# Untitled_b2.net
KiCad netlist of a schematic drawn in EAGLE
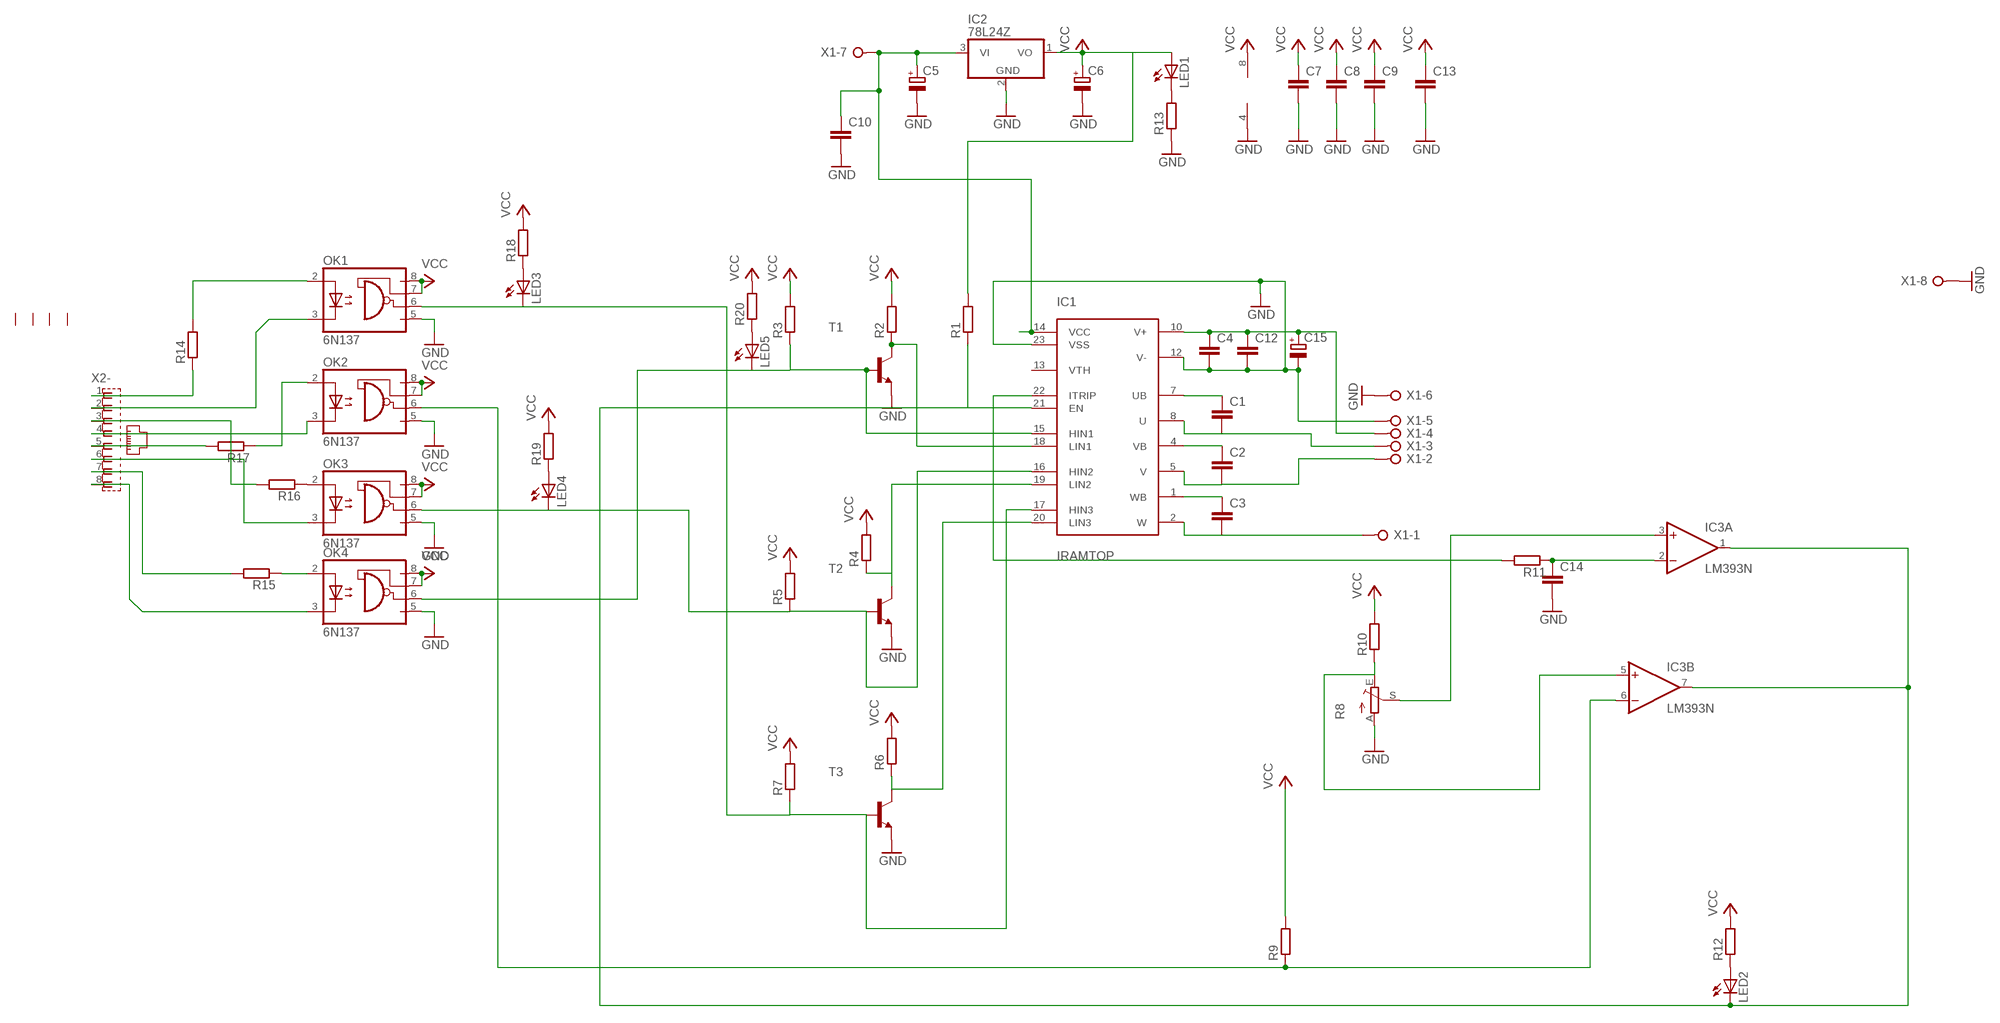
[diagram p0: schematic, sheet 1]

(export (version "E")
  (design (tool "Eeschema 10.0.6"))
  (components
    (comp (ref "C1")
      (value "C5/5")
      (footprint "eagle-import:C5B5")
      (libsource (lib "eagle-import") (part "C5/5"))
    )
    (comp (ref "C2")
      (value "C5/5")
      (footprint "eagle-import:C5B5")
      (libsource (lib "eagle-import") (part "C5/5"))
    )
    (comp (ref "C3")
      (value "C5/5")
      (footprint "eagle-import:C5B5")
      (libsource (lib "eagle-import") (part "C5/5"))
    )
    (comp (ref "C4")
      (value "C5/5")
      (footprint "eagle-import:C5B5")
      (libsource (lib "eagle-import") (part "C5/5"))
    )
    (comp (ref "C5")
      (value "CPOL-EUE2.5-5")
      (footprint "eagle-import:E2,5-5")
      (libsource (lib "eagle-import") (part "CPOL-EUE2.5-5"))
    )
    (comp (ref "C6")
      (value "CPOL-EUE2.5-5")
      (footprint "eagle-import:E2,5-5")
      (libsource (lib "eagle-import") (part "CPOL-EUE2.5-5"))
    )
    (comp (ref "C7")
      (value "C-EU050-025X075")
      (footprint "eagle-import:C050-025X075")
      (libsource (lib "eagle-import") (part "C-EU050-025X075"))
    )
    (comp (ref "C8")
      (value "C-EU050-025X075")
      (footprint "eagle-import:C050-025X075")
      (libsource (lib "eagle-import") (part "C-EU050-025X075"))
    )
    (comp (ref "C9")
      (value "C-EU050-025X075")
      (footprint "eagle-import:C050-025X075")
      (libsource (lib "eagle-import") (part "C-EU050-025X075"))
    )
    (comp (ref "C10")
      (value "C-EU050-025X075")
      (footprint "eagle-import:C050-025X075")
      (libsource (lib "eagle-import") (part "C-EU050-025X075"))
    )
    (comp (ref "C12")
      (value "C-EU150-054X183")
      (footprint "eagle-import:C150-054X183")
      (libsource (lib "eagle-import") (part "C-EU150-054X183"))
    )
    (comp (ref "C13")
      (value "C-EU050-025X075")
      (footprint "eagle-import:C050-025X075")
      (libsource (lib "eagle-import") (part "C-EU050-025X075"))
    )
    (comp (ref "C14")
      (value "C-EU050-025X075")
      (footprint "eagle-import:C050-025X075")
      (libsource (lib "eagle-import") (part "C-EU050-025X075"))
    )
    (comp (ref "C15")
      (value "CPOL-EUE10-25")
      (footprint "eagle-import:EB25D")
      (libsource (lib "eagle-import") (part "CPOL-EUE10-25"))
    )
    (comp (ref "IC1")
      (value "IRAMTOP")
      (footprint "eagle-import:SIP23_TOP")
      (libsource (lib "eagle-import") (part "IRAMTOP"))
    )
    (comp (ref "IC2")
      (value "78L24Z")
      (footprint "eagle-import:TO92")
      (libsource (lib "eagle-import") (part "78ZL24"))
    )
    (comp (ref "IC3")
      (value "LM393N")
      (footprint "eagle-import:DIL08")
      (libsource (lib "eagle-import") (part "LM393N"))
    )
    (comp (ref "LED1")
      (value "LED5MM")
      (footprint "eagle-import:LED5MM")
      (libsource (lib "eagle-import") (part "LED5MM"))
    )
    (comp (ref "LED2")
      (value "LED5MM")
      (footprint "eagle-import:LED5MM")
      (libsource (lib "eagle-import") (part "LED5MM"))
    )
    (comp (ref "LED3")
      (value "LED5MM")
      (footprint "eagle-import:LED5MM")
      (libsource (lib "eagle-import") (part "LED5MM"))
    )
    (comp (ref "LED4")
      (value "LED5MM")
      (footprint "eagle-import:LED5MM")
      (libsource (lib "eagle-import") (part "LED5MM"))
    )
    (comp (ref "LED5")
      (value "LED5MM")
      (footprint "eagle-import:LED5MM")
      (libsource (lib "eagle-import") (part "LED5MM"))
    )
    (comp (ref "OK1")
      (value "6N137")
      (footprint "eagle-import:DIL08")
      (libsource (lib "eagle-import") (part "6N137"))
    )
    (comp (ref "OK2")
      (value "6N137")
      (footprint "eagle-import:DIL08")
      (libsource (lib "eagle-import") (part "6N137"))
    )
    (comp (ref "OK3")
      (value "6N137")
      (footprint "eagle-import:DIL08")
      (libsource (lib "eagle-import") (part "6N137"))
    )
    (comp (ref "OK4")
      (value "6N137")
      (footprint "eagle-import:DIL08")
      (libsource (lib "eagle-import") (part "6N137"))
    )
    (comp (ref "R1")
      (value "R-EU_0204/7")
      (footprint "eagle-import:0204_7")
      (libsource (lib "eagle-import") (part "R-EU_0204/7"))
    )
    (comp (ref "R2")
      (value "R-EU_0204/7")
      (footprint "eagle-import:0204_7")
      (libsource (lib "eagle-import") (part "R-EU_0204/7"))
    )
    (comp (ref "R3")
      (value "R-EU_0204/7")
      (footprint "eagle-import:0204_7")
      (libsource (lib "eagle-import") (part "R-EU_0204/7"))
    )
    (comp (ref "R4")
      (value "R-EU_0204/7")
      (footprint "eagle-import:0204_7")
      (libsource (lib "eagle-import") (part "R-EU_0204/7"))
    )
    (comp (ref "R5")
      (value "R-EU_0204/7")
      (footprint "eagle-import:0204_7")
      (libsource (lib "eagle-import") (part "R-EU_0204/7"))
    )
    (comp (ref "R6")
      (value "R-EU_0204/7")
      (footprint "eagle-import:0204_7")
      (libsource (lib "eagle-import") (part "R-EU_0204/7"))
    )
    (comp (ref "R7")
      (value "R-EU_0204/7")
      (footprint "eagle-import:0204_7")
      (libsource (lib "eagle-import") (part "R-EU_0204/7"))
    )
    (comp (ref "R8")
      (value "TRIM_EU-CA6V")
      (footprint "eagle-import:CA6V")
      (libsource (lib "eagle-import") (part "TRIM_EU-CA6V"))
    )
    (comp (ref "R9")
      (value "R-EU_0204/7")
      (footprint "eagle-import:0204_7")
      (libsource (lib "eagle-import") (part "R-EU_0204/7"))
    )
    (comp (ref "R10")
      (value "R-EU_0204/7")
      (footprint "eagle-import:0204_7")
      (libsource (lib "eagle-import") (part "R-EU_0204/7"))
    )
    (comp (ref "R11")
      (value "R-EU_0204/7")
      (footprint "eagle-import:0204_7")
      (libsource (lib "eagle-import") (part "R-EU_0204/7"))
    )
    (comp (ref "R12")
      (value "R-EU_0204/7")
      (footprint "eagle-import:0204_7")
      (libsource (lib "eagle-import") (part "R-EU_0204/7"))
    )
    (comp (ref "R13")
      (value "R-EU_0204/7")
      (footprint "eagle-import:0204_7")
      (libsource (lib "eagle-import") (part "R-EU_0204/7"))
    )
    (comp (ref "R14")
      (value "R-EU_0204/2V")
      (footprint "eagle-import:0204V")
      (libsource (lib "eagle-import") (part "R-EU_0204/2V"))
    )
    (comp (ref "R15")
      (value "R-EU_0204/2V")
      (footprint "eagle-import:0204V")
      (libsource (lib "eagle-import") (part "R-EU_0204/2V"))
    )
    (comp (ref "R16")
      (value "R-EU_0204/2V")
      (footprint "eagle-import:0204V")
      (libsource (lib "eagle-import") (part "R-EU_0204/2V"))
    )
    (comp (ref "R17")
      (value "R-EU_0204/2V")
      (footprint "eagle-import:0204V")
      (libsource (lib "eagle-import") (part "R-EU_0204/2V"))
    )
    (comp (ref "R18")
      (value "R-EU_0204/7")
      (footprint "eagle-import:0204_7")
      (libsource (lib "eagle-import") (part "R-EU_0204/7"))
    )
    (comp (ref "R19")
      (value "R-EU_0204/7")
      (footprint "eagle-import:0204_7")
      (libsource (lib "eagle-import") (part "R-EU_0204/7"))
    )
    (comp (ref "R20")
      (value "R-EU_0204/7")
      (footprint "eagle-import:0204_7")
      (libsource (lib "eagle-import") (part "R-EU_0204/7"))
    )
    (comp (ref "T1")
      (value "BC547-NPN-TO92-CBE")
      (footprint "eagle-import:TO92-CBE")
      (libsource (lib "eagle-import") (part "-NPN-TO92-CBEBC547"))
    )
    (comp (ref "T2")
      (value "BC547-NPN-TO92-CBE")
      (footprint "eagle-import:TO92-CBE")
      (libsource (lib "eagle-import") (part "-NPN-TO92-CBEBC547"))
    )
    (comp (ref "T3")
      (value "BC547-NPN-TO92-CBE")
      (footprint "eagle-import:TO92-CBE")
      (libsource (lib "eagle-import") (part "-NPN-TO92-CBEBC547"))
    )
    (comp (ref "X1")
      (value "W237-08P")
      (footprint "eagle-import:W237-8P")
      (libsource (lib "eagle-import") (part "W237-08P"))
    )
    (comp (ref "X2")
      (value "RJ45")
      (footprint "eagle-import:RJ45")
      (libsource (lib "eagle-import") (part "RJ45"))
    )
  )
  (nets
    (net (code "1") (name "GND") (class "Default")
      (node (ref "C10") (pin "2") (pinfunction "2_2") (pintype "passive"))
      (node (ref "C12") (pin "2") (pinfunction "2_2") (pintype "passive"))
      (node (ref "C13") (pin "2") (pinfunction "2_2") (pintype "passive"))
      (node (ref "C14") (pin "2") (pinfunction "2_2") (pintype "passive"))
      (node (ref "C15") (pin "-") (pinfunction "-_-") (pintype "passive"))
      (node (ref "C4") (pin "2") (pinfunction "2_2") (pintype "passive"))
      (node (ref "C5") (pin "-") (pinfunction "-_-") (pintype "passive"))
      (node (ref "C6") (pin "-") (pinfunction "-_-") (pintype "passive"))
      (node (ref "C7") (pin "2") (pinfunction "2_2") (pintype "passive"))
      (node (ref "C8") (pin "2") (pinfunction "2_2") (pintype "passive"))
      (node (ref "C9") (pin "2") (pinfunction "2_2") (pintype "passive"))
      (node (ref "IC1") (pin "12") (pinfunction "V-_12") (pintype "bidirectional"))
      (node (ref "IC1") (pin "23") (pinfunction "VSS_23") (pintype "bidirectional"))
      (node (ref "IC2") (pin "2") (pinfunction "GND_2") (pintype "passive"))
      (node (ref "IC3") (pin "4") (pinfunction "V-_4") (pintype "power_in"))
      (node (ref "OK1") (pin "5") (pinfunction "GND_5") (pintype "passive"))
      (node (ref "OK2") (pin "5") (pinfunction "GND_5") (pintype "passive"))
      (node (ref "OK3") (pin "5") (pinfunction "GND_5") (pintype "passive"))
      (node (ref "OK4") (pin "5") (pinfunction "GND_5") (pintype "passive"))
      (node (ref "R13") (pin "1") (pinfunction "1_1") (pintype "passive"))
      (node (ref "R8") (pin "A") (pinfunction "A_A") (pintype "passive"))
      (node (ref "T1") (pin "E") (pinfunction "E_E") (pintype "passive"))
      (node (ref "T2") (pin "E") (pinfunction "E_E") (pintype "passive"))
      (node (ref "T3") (pin "E") (pinfunction "E_E") (pintype "passive"))
      (node (ref "X1") (pin "5") (pinfunction "KL_5") (pintype "passive"))
      (node (ref "X1") (pin "6") (pinfunction "KL_6") (pintype "passive"))
      (node (ref "X1") (pin "8") (pinfunction "KL_8") (pintype "passive"))
    )
    (net (code "2") (name "Net-(IC1-EN)") (class "Default")
      (node (ref "IC1") (pin "21") (pinfunction "EN_21") (pintype "bidirectional"))
      (node (ref "IC3") (pin "1") (pinfunction "OUT_1") (pintype "output"))
      (node (ref "IC3") (pin "7") (pinfunction "OUT_7") (pintype "output"))
      (node (ref "LED2") (pin "K") (pinfunction "C_K") (pintype "passive"))
      (node (ref "R1") (pin "1") (pinfunction "1_1") (pintype "passive"))
    )
    (net (code "3") (name "Net-(IC1-HIN1)") (class "Default")
      (node (ref "IC1") (pin "15") (pinfunction "HIN1_15") (pintype "bidirectional"))
      (node (ref "OK4") (pin "6") (pinfunction "VO_6") (pintype "passive"))
      (node (ref "R3") (pin "1") (pinfunction "1_1") (pintype "passive"))
      (node (ref "T1") (pin "B") (pinfunction "B_B") (pintype "passive"))
    )
    (net (code "4") (name "Net-(IC1-HIN2)") (class "Default")
      (node (ref "IC1") (pin "16") (pinfunction "HIN2_16") (pintype "bidirectional"))
      (node (ref "OK3") (pin "6") (pinfunction "VO_6") (pintype "passive"))
      (node (ref "R5") (pin "1") (pinfunction "1_1") (pintype "passive"))
      (node (ref "T2") (pin "B") (pinfunction "B_B") (pintype "passive"))
    )
    (net (code "5") (name "Net-(IC1-HIN3)") (class "Default")
      (node (ref "IC1") (pin "17") (pinfunction "HIN3_17") (pintype "bidirectional"))
      (node (ref "OK1") (pin "6") (pinfunction "VO_6") (pintype "passive"))
      (node (ref "R7") (pin "1") (pinfunction "1_1") (pintype "passive"))
      (node (ref "T3") (pin "B") (pinfunction "B_B") (pintype "passive"))
    )
    (net (code "6") (name "Net-(IC1-ITRIP)") (class "Default")
      (node (ref "IC1") (pin "22") (pinfunction "ITRIP_22") (pintype "bidirectional"))
      (node (ref "R11") (pin "2") (pinfunction "2_2") (pintype "passive"))
    )
    (net (code "7") (name "Net-(IC1-LIN1)") (class "Default")
      (node (ref "IC1") (pin "18") (pinfunction "LIN1_18") (pintype "bidirectional"))
      (node (ref "R2") (pin "1") (pinfunction "1_1") (pintype "passive"))
      (node (ref "T1") (pin "C") (pinfunction "C_C") (pintype "passive"))
    )
    (net (code "8") (name "Net-(IC1-LIN2)") (class "Default")
      (node (ref "IC1") (pin "19") (pinfunction "LIN2_19") (pintype "bidirectional"))
      (node (ref "R4") (pin "1") (pinfunction "1_1") (pintype "passive"))
      (node (ref "T2") (pin "C") (pinfunction "C_C") (pintype "passive"))
    )
    (net (code "9") (name "Net-(IC1-LIN3)") (class "Default")
      (node (ref "IC1") (pin "20") (pinfunction "LIN3_20") (pintype "bidirectional"))
      (node (ref "R6") (pin "1") (pinfunction "1_1") (pintype "passive"))
      (node (ref "T3") (pin "C") (pinfunction "C_C") (pintype "passive"))
    )
    (net (code "10") (name "Net-(IC1-U)") (class "Default")
      (node (ref "C1") (pin "2") (pinfunction "2_2") (pintype "passive"))
      (node (ref "IC1") (pin "8") (pinfunction "U_8") (pintype "bidirectional"))
      (node (ref "X1") (pin "3") (pinfunction "KL_3") (pintype "passive"))
    )
    (net (code "11") (name "Net-(IC1-UB)") (class "Default")
      (node (ref "C1") (pin "1") (pinfunction "1_1") (pintype "passive"))
      (node (ref "IC1") (pin "7") (pinfunction "UB_7") (pintype "bidirectional"))
    )
    (net (code "12") (name "Net-(IC1-V)") (class "Default")
      (node (ref "C2") (pin "2") (pinfunction "2_2") (pintype "passive"))
      (node (ref "IC1") (pin "5") (pinfunction "V_5") (pintype "bidirectional"))
      (node (ref "X1") (pin "2") (pinfunction "KL_2") (pintype "passive"))
    )
    (net (code "13") (name "Net-(IC1-V+)") (class "Default")
      (node (ref "C12") (pin "1") (pinfunction "1_1") (pintype "passive"))
      (node (ref "C15") (pin "+") (pinfunction "+_+") (pintype "passive"))
      (node (ref "C4") (pin "1") (pinfunction "1_1") (pintype "passive"))
      (node (ref "IC1") (pin "10") (pinfunction "V+_10") (pintype "bidirectional"))
      (node (ref "X1") (pin "4") (pinfunction "KL_4") (pintype "passive"))
    )
    (net (code "14") (name "Net-(IC1-VB)") (class "Default")
      (node (ref "C2") (pin "1") (pinfunction "1_1") (pintype "passive"))
      (node (ref "IC1") (pin "4") (pinfunction "VB_4") (pintype "bidirectional"))
    )
    (net (code "15") (name "Net-(IC1-VCC)") (class "Default")
      (node (ref "C10") (pin "1") (pinfunction "1_1") (pintype "passive"))
      (node (ref "C5") (pin "+") (pinfunction "+_+") (pintype "passive"))
      (node (ref "IC1") (pin "14") (pinfunction "VCC_14") (pintype "bidirectional"))
      (node (ref "IC2") (pin "3") (pinfunction "VI_3") (pintype "input"))
      (node (ref "X1") (pin "7") (pinfunction "KL_7") (pintype "passive"))
    )
    (net (code "16") (name "Net-(IC1-W)") (class "Default")
      (node (ref "C3") (pin "2") (pinfunction "2_2") (pintype "passive"))
      (node (ref "IC1") (pin "2") (pinfunction "W_2") (pintype "bidirectional"))
      (node (ref "X1") (pin "1") (pinfunction "KL_1") (pintype "passive"))
    )
    (net (code "17") (name "Net-(IC1-WB)") (class "Default")
      (node (ref "C3") (pin "1") (pinfunction "1_1") (pintype "passive"))
      (node (ref "IC1") (pin "1") (pinfunction "WB_1") (pintype "bidirectional"))
    )
    (net (code "18") (name "Net-(IC3A-+IN)") (class "Default")
      (node (ref "IC3") (pin "3") (pinfunction "+IN_3") (pintype "input"))
      (node (ref "R8") (pin "S") (pinfunction "S_S") (pintype "passive"))
    )
    (net (code "19") (name "Net-(IC3A--IN)") (class "Default")
      (node (ref "C14") (pin "1") (pinfunction "1_1") (pintype "passive"))
      (node (ref "IC3") (pin "2") (pinfunction "-IN_2") (pintype "input"))
      (node (ref "R11") (pin "1") (pinfunction "1_1") (pintype "passive"))
    )
    (net (code "20") (name "Net-(IC3B-+IN)") (class "Default")
      (node (ref "IC3") (pin "5") (pinfunction "+IN_5") (pintype "input"))
      (node (ref "R10") (pin "1") (pinfunction "1_1") (pintype "passive"))
      (node (ref "R8") (pin "E") (pinfunction "E_E") (pintype "passive"))
    )
    (net (code "21") (name "Net-(IC3B--IN)") (class "Default")
      (node (ref "IC3") (pin "6") (pinfunction "-IN_6") (pintype "input"))
      (node (ref "OK2") (pin "6") (pinfunction "VO_6") (pintype "passive"))
      (node (ref "R9") (pin "1") (pinfunction "1_1") (pintype "passive"))
    )
    (net (code "22") (name "Net-(LED1-C)") (class "Default")
      (node (ref "LED1") (pin "K") (pinfunction "C_K") (pintype "passive"))
      (node (ref "R13") (pin "2") (pinfunction "2_2") (pintype "passive"))
    )
    (net (code "23") (name "Net-(LED2-PadA)") (class "Default")
      (node (ref "LED2") (pin "A") (pinfunction "A_A") (pintype "passive"))
      (node (ref "R12") (pin "1") (pinfunction "1_1") (pintype "passive"))
    )
    (net (code "24") (name "Net-(LED3-PadA)") (class "Default")
      (node (ref "LED3") (pin "A") (pinfunction "A_A") (pintype "passive"))
      (node (ref "R18") (pin "1") (pinfunction "1_1") (pintype "passive"))
    )
    (net (code "25") (name "Net-(LED4-PadA)") (class "Default")
      (node (ref "LED4") (pin "A") (pinfunction "A_A") (pintype "passive"))
      (node (ref "R19") (pin "1") (pinfunction "1_1") (pintype "passive"))
    )
    (net (code "26") (name "Net-(LED5-PadA)") (class "Default")
      (node (ref "LED5") (pin "A") (pinfunction "A_A") (pintype "passive"))
      (node (ref "R20") (pin "1") (pinfunction "1_1") (pintype "passive"))
    )
    (net (code "27") (name "Net-(OK1-A)") (class "Default")
      (node (ref "OK1") (pin "2") (pinfunction "A_2") (pintype "passive"))
      (node (ref "R14") (pin "2") (pinfunction "2_2") (pintype "passive"))
    )
    (net (code "28") (name "Net-(OK1-C)") (class "Default")
      (node (ref "OK1") (pin "3") (pinfunction "C_3") (pintype "passive"))
      (node (ref "X2") (pin "2") (pinfunction "2_2") (pintype "passive"))
    )
    (net (code "29") (name "Net-(OK2-A)") (class "Default")
      (node (ref "OK2") (pin "2") (pinfunction "A_2") (pintype "passive"))
      (node (ref "R17") (pin "1") (pinfunction "1_1") (pintype "passive"))
    )
    (net (code "30") (name "Net-(OK2-C)") (class "Default")
      (node (ref "OK2") (pin "3") (pinfunction "C_3") (pintype "passive"))
      (node (ref "X2") (pin "4") (pinfunction "4_4") (pintype "passive"))
    )
    (net (code "31") (name "Net-(OK3-A)") (class "Default")
      (node (ref "OK3") (pin "2") (pinfunction "A_2") (pintype "passive"))
      (node (ref "R16") (pin "1") (pinfunction "1_1") (pintype "passive"))
    )
    (net (code "32") (name "Net-(OK3-C)") (class "Default")
      (node (ref "OK3") (pin "3") (pinfunction "C_3") (pintype "passive"))
      (node (ref "X2") (pin "6") (pinfunction "6_6") (pintype "passive"))
    )
    (net (code "33") (name "Net-(OK4-A)") (class "Default")
      (node (ref "OK4") (pin "2") (pinfunction "A_2") (pintype "passive"))
      (node (ref "R15") (pin "1") (pinfunction "1_1") (pintype "passive"))
    )
    (net (code "34") (name "Net-(OK4-C)") (class "Default")
      (node (ref "OK4") (pin "3") (pinfunction "C_3") (pintype "passive"))
      (node (ref "X2") (pin "8") (pinfunction "8_8") (pintype "passive"))
    )
    (net (code "35") (name "Net-(R14-Pad1)") (class "Default")
      (node (ref "R14") (pin "1") (pinfunction "1_1") (pintype "passive"))
      (node (ref "X2") (pin "1") (pinfunction "1_1") (pintype "passive"))
    )
    (net (code "36") (name "Net-(R15-Pad2)") (class "Default")
      (node (ref "R15") (pin "2") (pinfunction "2_2") (pintype "passive"))
      (node (ref "X2") (pin "7") (pinfunction "7_7") (pintype "passive"))
    )
    (net (code "37") (name "Net-(R16-Pad2)") (class "Default")
      (node (ref "R16") (pin "2") (pinfunction "2_2") (pintype "passive"))
      (node (ref "X2") (pin "3") (pinfunction "3_3") (pintype "passive"))
    )
    (net (code "38") (name "Net-(R17-Pad2)") (class "Default")
      (node (ref "R17") (pin "2") (pinfunction "2_2") (pintype "passive"))
      (node (ref "X2") (pin "5") (pinfunction "5_5") (pintype "passive"))
    )
    (net (code "39") (name "VCC") (class "Default")
      (node (ref "C13") (pin "1") (pinfunction "1_1") (pintype "passive"))
      (node (ref "C6") (pin "+") (pinfunction "+_+") (pintype "passive"))
      (node (ref "C7") (pin "1") (pinfunction "1_1") (pintype "passive"))
      (node (ref "C8") (pin "1") (pinfunction "1_1") (pintype "passive"))
      (node (ref "C9") (pin "1") (pinfunction "1_1") (pintype "passive"))
      (node (ref "IC2") (pin "1") (pinfunction "VO_1") (pintype "passive"))
      (node (ref "IC3") (pin "8") (pinfunction "V+_8") (pintype "power_in"))
      (node (ref "LED1") (pin "A") (pinfunction "A_A") (pintype "passive"))
      (node (ref "OK1") (pin "7") (pinfunction "VE_7") (pintype "passive"))
      (node (ref "OK1") (pin "8") (pinfunction "VCC_8") (pintype "passive"))
      (node (ref "OK2") (pin "7") (pinfunction "VE_7") (pintype "passive"))
      (node (ref "OK2") (pin "8") (pinfunction "VCC_8") (pintype "passive"))
      (node (ref "OK3") (pin "7") (pinfunction "VE_7") (pintype "passive"))
      (node (ref "OK3") (pin "8") (pinfunction "VCC_8") (pintype "passive"))
      (node (ref "OK4") (pin "7") (pinfunction "VE_7") (pintype "passive"))
      (node (ref "OK4") (pin "8") (pinfunction "VCC_8") (pintype "passive"))
      (node (ref "R1") (pin "2") (pinfunction "2_2") (pintype "passive"))
      (node (ref "R10") (pin "2") (pinfunction "2_2") (pintype "passive"))
      (node (ref "R12") (pin "2") (pinfunction "2_2") (pintype "passive"))
      (node (ref "R18") (pin "2") (pinfunction "2_2") (pintype "passive"))
      (node (ref "R19") (pin "2") (pinfunction "2_2") (pintype "passive"))
      (node (ref "R2") (pin "2") (pinfunction "2_2") (pintype "passive"))
      (node (ref "R20") (pin "2") (pinfunction "2_2") (pintype "passive"))
      (node (ref "R3") (pin "2") (pinfunction "2_2") (pintype "passive"))
      (node (ref "R4") (pin "2") (pinfunction "2_2") (pintype "passive"))
      (node (ref "R5") (pin "2") (pinfunction "2_2") (pintype "passive"))
      (node (ref "R6") (pin "2") (pinfunction "2_2") (pintype "passive"))
      (node (ref "R7") (pin "2") (pinfunction "2_2") (pintype "passive"))
      (node (ref "R9") (pin "2") (pinfunction "2_2") (pintype "passive"))
    )
    (net (code "40") (name "unconnected-(IC1-VTH-Pad13)") (class "Default")
      (node (ref "IC1") (pin "13") (pinfunction "VTH_13") (pintype "bidirectional"))
    )
    (net (code "41") (name "unconnected-(LED3-C-PadK)") (class "Default")
      (node (ref "LED3") (pin "K") (pinfunction "C_K") (pintype "passive"))
    )
    (net (code "42") (name "unconnected-(LED4-C-PadK)") (class "Default")
      (node (ref "LED4") (pin "K") (pinfunction "C_K") (pintype "passive"))
    )
    (net (code "43") (name "unconnected-(LED5-C-PadK)") (class "Default")
      (node (ref "LED5") (pin "K") (pinfunction "C_K") (pintype "passive"))
    )
    (net (code "44") (name "unconnected-(X2B-1-PadG1)") (class "Default")
      (node (ref "X2") (pin "G1") (pinfunction "1_G1") (pintype "passive"))
    )
    (net (code "45") (name "unconnected-(X2C-1-PadG2)") (class "Default")
      (node (ref "X2") (pin "G2") (pinfunction "1_G2") (pintype "passive"))
    )
    (net (code "46") (name "unconnected-(X2D-1-PadG3)") (class "Default")
      (node (ref "X2") (pin "G3") (pinfunction "1_G3") (pintype "passive"))
    )
    (net (code "47") (name "unconnected-(X2E-1-PadG4)") (class "Default")
      (node (ref "X2") (pin "G4") (pinfunction "1_G4") (pintype "passive"))
    )
  )
)
